# ISP_Arduino_Board.net
KiCad netlist of a schematic drawn in EAGLE
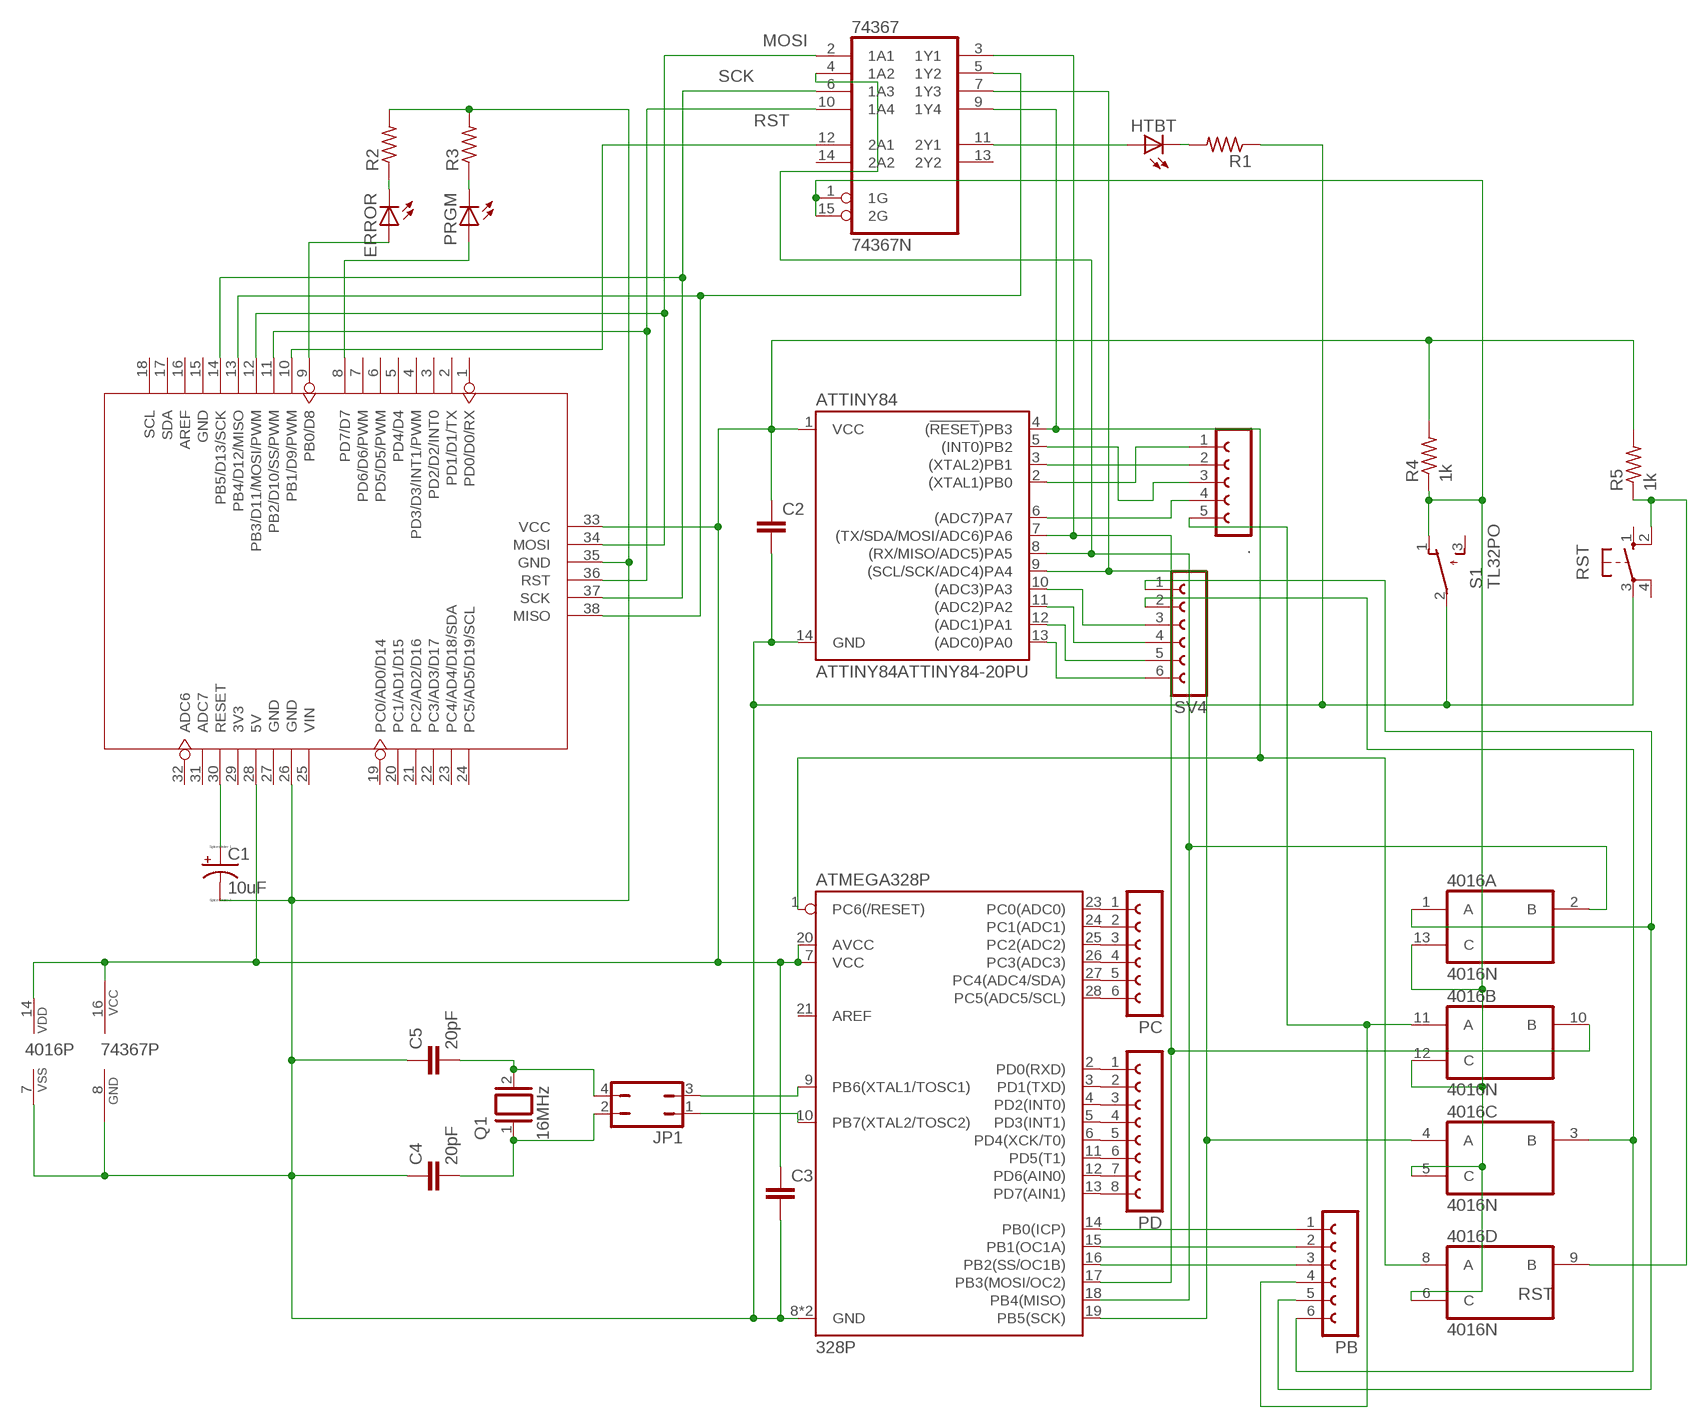
[diagram p0: schematic, sheet 1]

(export (version "E")
  (design (tool "Eeschema 10.0.6"))
  (components
    (comp (ref ".")
      (value "FE05-1")
      (footprint "eagle-import:FE05-1")
      (libsource (lib "eagle-import") (part "FE05-1"))
    )
    (comp (ref "4016")
      (value "4016N")
      (footprint "eagle-import:DIL14")
      (libsource (lib "eagle-import") (part "4016N"))
    )
    (comp (ref "74367")
      (value "74367N")
      (footprint "eagle-import:DIL16")
      (libsource (lib "eagle-import") (part "74367N"))
    )
    (comp (ref "ATMEGA328P")
      (value "328P")
      (footprint "eagle-import:DIP28")
      (libsource (lib "eagle-import") (part "ATMEGA328P_PDIP"))
    )
    (comp (ref "ATTINY84")
      (value "ATTINY84ATTINY84-20PU")
      (footprint "eagle-import:DIP14")
      (libsource (lib "eagle-import") (part "ATTINY84ATTINY84-20PU"))
    )
    (comp (ref "C1")
      (value "10uF")
      (footprint "eagle-import:E2,5-6")
      (libsource (lib "eagle-import") (part "CPOL-USE2.5-6"))
    )
    (comp (ref "C2")
      (value "C2,5-3")
      (footprint "eagle-import:C2.5-3")
      (libsource (lib "eagle-import") (part "C2,5-3"))
    )
    (comp (ref "C3")
      (value "C2,5-3")
      (footprint "eagle-import:C2.5-3")
      (libsource (lib "eagle-import") (part "C2,5-3"))
    )
    (comp (ref "C4")
      (value "20pF")
      (footprint "eagle-import:C2.5-3")
      (libsource (lib "eagle-import") (part "C2,5-3"))
    )
    (comp (ref "C5")
      (value "20pF")
      (footprint "eagle-import:C2.5-3")
      (libsource (lib "eagle-import") (part "C2,5-3"))
    )
    (comp (ref "ERROR")
      (value "LED3MM")
      (footprint "eagle-import:LED3MM")
      (libsource (lib "eagle-import") (part "LED3MM"))
    )
    (comp (ref "HTBT")
      (value "LED3MM")
      (footprint "eagle-import:LED3MM")
      (libsource (lib "eagle-import") (part "LED3MM"))
    )
    (comp (ref "JP1")
      (value "JP2Q")
      (footprint "eagle-import:JP2Q")
      (libsource (lib "eagle-import") (part "JP2Q"))
    )
    (comp (ref "PB")
      (value "FE06-1")
      (footprint "eagle-import:FE06")
      (libsource (lib "eagle-import") (part "FE06-1"))
    )
    (comp (ref "PC")
      (value "FE06-1")
      (footprint "eagle-import:FE06")
      (libsource (lib "eagle-import") (part "FE06-1"))
    )
    (comp (ref "PD")
      (value "FE08-1")
      (footprint "eagle-import:FE08")
      (libsource (lib "eagle-import") (part "FE08-1"))
    )
    (comp (ref "PRGM")
      (value "LED3MM")
      (footprint "eagle-import:LED3MM")
      (libsource (lib "eagle-import") (part "LED3MM"))
    )
    (comp (ref "Q1")
      (value "16MHz")
      (footprint "eagle-import:QS")
      (libsource (lib "eagle-import") (part "XTAL/S"))
    )
    (comp (ref "R1")
      (value "R-US_0207/10")
      (footprint "eagle-import:0207_10")
      (libsource (lib "eagle-import") (part "R-US_0207/10"))
    )
    (comp (ref "R2")
      (value "R-US_0207/10")
      (footprint "eagle-import:0207_10")
      (libsource (lib "eagle-import") (part "R-US_0207/10"))
    )
    (comp (ref "R3")
      (value "R-US_0207/10")
      (footprint "eagle-import:0207_10")
      (libsource (lib "eagle-import") (part "R-US_0207/10"))
    )
    (comp (ref "R4")
      (value "1k")
      (footprint "eagle-import:0207_10")
      (libsource (lib "eagle-import") (part "R-US_0207/10"))
    )
    (comp (ref "R5")
      (value "1k")
      (footprint "eagle-import:0207_10")
      (libsource (lib "eagle-import") (part "R-US_0207/10"))
    )
    (comp (ref "RST")
      (value "10-XX")
      (footprint "eagle-import:B3F-10XX")
      (fields (field (name "MPN") "B3F-1000"))
      (libsource (lib "eagle-import") (part "10-XX"))
    )
    (comp (ref "S1")
      (value "TL32PO")
      (footprint "eagle-import:TL3XPO")
      (libsource (lib "eagle-import") (part "TL32PO"))
    )
    (comp (ref "SV4")
      (value "FE06-1")
      (footprint "eagle-import:FE06")
      (libsource (lib "eagle-import") (part "FE06-1"))
    )
    (comp (ref "U2")
      (value "DIP Long Blue Female Header")
      (footprint "eagle-import:ARDUINO-38P")
      (libsource (lib "eagle-import") (part "ARDUINO-38P"))
    )
  )
  (nets
    (net (code "1") (name "Net-(4016A-A)") (class "Default")
      (node (ref "4016") (pin "1") (pinfunction "A_1") (pintype "tri_state"))
      (node (ref "PB") (pin "5") (pinfunction "5_5") (pintype "passive"))
      (node (ref "SV4") (pin "1") (pinfunction "1_1") (pintype "passive"))
    )
    (net (code "2") (name "Net-(4016A-B)") (class "Default")
      (node (ref "4016") (pin "2") (pinfunction "B_2") (pintype "tri_state"))
      (node (ref "74367") (pin "4") (pinfunction "1A2_4") (pintype "input"))
      (node (ref "ATMEGA328P") (pin "18") (pinfunction "PB4(MISO)_18") (pintype "bidirectional"))
      (node (ref "ATTINY84") (pin "8") (pinfunction "(RX/MISO/ADC5)PA5_8") (pintype "bidirectional"))
    )
    (net (code "3") (name "Net-(4016A-C)") (class "Default")
      (node (ref "4016") (pin "12") (pinfunction "C_12") (pintype "input"))
      (node (ref "4016") (pin "13") (pinfunction "C_13") (pintype "input"))
      (node (ref "4016") (pin "5") (pinfunction "C_5") (pintype "input"))
      (node (ref "4016") (pin "6") (pinfunction "C_6") (pintype "input"))
      (node (ref "74367") (pin "1") (pinfunction "1G_1") (pintype "input"))
      (node (ref "74367") (pin "15") (pinfunction "2G_15") (pintype "input"))
      (node (ref "R4") (pin "1") (pinfunction "1_1") (pintype "passive"))
      (node (ref "S1") (pin "1") (pinfunction "O_1") (pintype "passive"))
    )
    (net (code "4") (name "Net-(4016B-A)") (class "Default")
      (node (ref ".") (pin "5") (pinfunction "5_5") (pintype "passive"))
      (node (ref "4016") (pin "11") (pinfunction "A_11") (pintype "tri_state"))
      (node (ref "PB") (pin "4") (pinfunction "4_4") (pintype "passive"))
    )
    (net (code "5") (name "Net-(4016B-B)") (class "Default")
      (node (ref "4016") (pin "10") (pinfunction "B_10") (pintype "tri_state"))
      (node (ref "74367") (pin "3") (pinfunction "1Y1_3") (pintype "tri_state"))
      (node (ref "ATMEGA328P") (pin "17") (pinfunction "PB3(MOSI/OC2)_17") (pintype "bidirectional"))
      (node (ref "ATTINY84") (pin "7") (pinfunction "(TX/SDA/MOSI/ADC6)PA6_7") (pintype "bidirectional"))
    )
    (net (code "6") (name "Net-(4016C-A)") (class "Default")
      (node (ref "4016") (pin "4") (pinfunction "A_4") (pintype "tri_state"))
      (node (ref "74367") (pin "7") (pinfunction "1Y3_7") (pintype "tri_state"))
      (node (ref "ATMEGA328P") (pin "19") (pinfunction "PB5(SCK)_19") (pintype "bidirectional"))
      (node (ref "ATTINY84") (pin "9") (pinfunction "(SCL/SCK/ADC4)PA4_9") (pintype "bidirectional"))
    )
    (net (code "7") (name "Net-(4016C-B)") (class "Default")
      (node (ref "4016") (pin "3") (pinfunction "B_3") (pintype "tri_state"))
      (node (ref "PB") (pin "6") (pinfunction "6_6") (pintype "passive"))
      (node (ref "SV4") (pin "2") (pinfunction "2_2") (pintype "passive"))
    )
    (net (code "8") (name "Net-(4016D-B)") (class "Default")
      (node (ref "4016") (pin "9") (pinfunction "B_9") (pintype "tri_state"))
      (node (ref "R5") (pin "1") (pinfunction "1_1") (pintype "passive"))
      (node (ref "RST") (pin "2") (pinfunction "S1_2") (pintype "passive"))
    )
    (net (code "9") (name "Net-(4016E-VDD)") (class "Default")
      (node (ref "4016") (pin "14") (pinfunction "VDD_14") (pintype "power_in"))
      (node (ref "74367") (pin "16") (pinfunction "VCC_16") (pintype "power_in"))
      (node (ref "ATMEGA328P") (pin "20") (pinfunction "AVCC_20") (pintype "bidirectional"))
      (node (ref "ATMEGA328P") (pin "7") (pinfunction "VCC_7") (pintype "bidirectional"))
      (node (ref "ATTINY84") (pin "1") (pinfunction "VCC_1") (pintype "bidirectional"))
      (node (ref "C2") (pin "1") (pinfunction "1_1") (pintype "passive"))
      (node (ref "C3") (pin "1") (pinfunction "1_1") (pintype "passive"))
      (node (ref "R4") (pin "2") (pinfunction "2_2") (pintype "passive"))
      (node (ref "R5") (pin "2") (pinfunction "2_2") (pintype "passive"))
      (node (ref "U2") (pin "28") (pinfunction "5V_28") (pintype "bidirectional"))
      (node (ref "U2") (pin "33") (pinfunction "VCC_33") (pintype "bidirectional"))
    )
    (net (code "10") (name "Net-(4016E-VSS)") (class "Default")
      (node (ref "4016") (pin "7") (pinfunction "VSS_7") (pintype "power_in"))
      (node (ref "74367") (pin "8") (pinfunction "GND_8") (pintype "power_in"))
      (node (ref "ATMEGA328P") (pin "22") (pinfunction "GND_22") (pintype "bidirectional"))
      (node (ref "ATMEGA328P") (pin "8") (pinfunction "GND_8") (pintype "bidirectional"))
      (node (ref "ATTINY84") (pin "14") (pinfunction "GND_14") (pintype "bidirectional"))
      (node (ref "C1") (pin "-") (pinfunction "-_-") (pintype "passive"))
      (node (ref "C2") (pin "2") (pinfunction "2_2") (pintype "passive"))
      (node (ref "C3") (pin "2") (pinfunction "2_2") (pintype "passive"))
      (node (ref "C4") (pin "1") (pinfunction "1_1") (pintype "passive"))
      (node (ref "C5") (pin "1") (pinfunction "1_1") (pintype "passive"))
      (node (ref "R1") (pin "1") (pinfunction "1_1") (pintype "passive"))
      (node (ref "R2") (pin "2") (pinfunction "2_2") (pintype "passive"))
      (node (ref "R3") (pin "2") (pinfunction "2_2") (pintype "passive"))
      (node (ref "RST") (pin "3") (pinfunction "P_3") (pintype "passive"))
      (node (ref "S1") (pin "2") (pinfunction "P_2") (pintype "passive"))
      (node (ref "U2") (pin "26") (pinfunction "GND_26") (pintype "bidirectional"))
      (node (ref "U2") (pin "35") (pinfunction "GND_35") (pintype "bidirectional"))
    )
    (net (code "11") (name "Net-(74367A-1A1)") (class "Default")
      (node (ref "74367") (pin "2") (pinfunction "1A1_2") (pintype "input"))
      (node (ref "U2") (pin "12") (pinfunction "PB3/D11/MOSI/PWM_12") (pintype "bidirectional"))
      (node (ref "U2") (pin "34") (pinfunction "MOSI_34") (pintype "bidirectional"))
    )
    (net (code "12") (name "Net-(74367A-1A3)") (class "Default")
      (node (ref "74367") (pin "6") (pinfunction "1A3_6") (pintype "input"))
      (node (ref "U2") (pin "14") (pinfunction "PB5/D13/SCK_14") (pintype "bidirectional"))
      (node (ref "U2") (pin "37") (pinfunction "SCK_37") (pintype "bidirectional"))
    )
    (net (code "13") (name "Net-(74367A-1A4)") (class "Default")
      (node (ref "74367") (pin "10") (pinfunction "1A4_10") (pintype "input"))
      (node (ref "U2") (pin "11") (pinfunction "PB2/D10/SS/PWM_11") (pintype "bidirectional"))
      (node (ref "U2") (pin "36") (pinfunction "RST_36") (pintype "bidirectional"))
    )
    (net (code "14") (name "Net-(74367A-1Y2)") (class "Default")
      (node (ref "74367") (pin "5") (pinfunction "1Y2_5") (pintype "tri_state"))
      (node (ref "U2") (pin "13") (pinfunction "PB4/D12/MISO_13") (pintype "bidirectional"))
      (node (ref "U2") (pin "38") (pinfunction "MISO_38") (pintype "bidirectional"))
    )
    (net (code "15") (name "Net-(74367A-1Y4)") (class "Default")
      (node (ref "74367") (pin "9") (pinfunction "1Y4_9") (pintype "tri_state"))
      (node (ref "ATMEGA328P") (pin "1") (pinfunction "PC6(/RESET)_1") (pintype "bidirectional"))
      (node (ref "ATTINY84") (pin "4") (pinfunction "(~{RESET})PB3_4") (pintype "bidirectional"))
    )
    (net (code "16") (name "Net-(74367A-2A1)") (class "Default")
      (node (ref "74367") (pin "12") (pinfunction "2A1_12") (pintype "input"))
      (node (ref "U2") (pin "10") (pinfunction "PB1/D9/PWM_10") (pintype "bidirectional"))
    )
    (net (code "17") (name "Net-(74367A-2Y1)") (class "Default")
      (node (ref "74367") (pin "11") (pinfunction "2Y1_11") (pintype "tri_state"))
      (node (ref "HTBT") (pin "A") (pinfunction "A_A") (pintype "passive"))
    )
    (net (code "18") (name "Net-(ATMEGA328P-PB0(ICP))") (class "Default")
      (node (ref "ATMEGA328P") (pin "14") (pinfunction "PB0(ICP)_14") (pintype "bidirectional"))
      (node (ref "PB") (pin "1") (pinfunction "1_1") (pintype "passive"))
    )
    (net (code "19") (name "Net-(ATMEGA328P-PB1(OC1A))") (class "Default")
      (node (ref "ATMEGA328P") (pin "15") (pinfunction "PB1(OC1A)_15") (pintype "bidirectional"))
      (node (ref "PB") (pin "2") (pinfunction "2_2") (pintype "passive"))
    )
    (net (code "20") (name "Net-(ATMEGA328P-PB2(SS{slash}OC1B))") (class "Default")
      (node (ref "ATMEGA328P") (pin "16") (pinfunction "PB2(SS/OC1B)_16") (pintype "bidirectional"))
      (node (ref "PB") (pin "3") (pinfunction "3_3") (pintype "passive"))
    )
    (net (code "21") (name "Net-(ATMEGA328P-PB6(XTAL1{slash}TOSC1))") (class "Default")
      (node (ref "ATMEGA328P") (pin "9") (pinfunction "PB6(XTAL1/TOSC1)_9") (pintype "bidirectional"))
      (node (ref "JP1") (pin "3") (pinfunction "3_3") (pintype "passive"))
    )
    (net (code "22") (name "Net-(ATMEGA328P-PB7(XTAL2{slash}TOSC2))") (class "Default")
      (node (ref "ATMEGA328P") (pin "10") (pinfunction "PB7(XTAL2/TOSC2)_10") (pintype "bidirectional"))
      (node (ref "JP1") (pin "1") (pinfunction "1_1") (pintype "passive"))
    )
    (net (code "23") (name "Net-(ATMEGA328P-PC0(ADC0))") (class "Default")
      (node (ref "ATMEGA328P") (pin "23") (pinfunction "PC0(ADC0)_23") (pintype "bidirectional"))
      (node (ref "PC") (pin "1") (pinfunction "1_1") (pintype "passive"))
    )
    (net (code "24") (name "Net-(ATMEGA328P-PC1(ADC1))") (class "Default")
      (node (ref "ATMEGA328P") (pin "24") (pinfunction "PC1(ADC1)_24") (pintype "bidirectional"))
      (node (ref "PC") (pin "2") (pinfunction "2_2") (pintype "passive"))
    )
    (net (code "25") (name "Net-(ATMEGA328P-PC2(ADC2))") (class "Default")
      (node (ref "ATMEGA328P") (pin "25") (pinfunction "PC2(ADC2)_25") (pintype "bidirectional"))
      (node (ref "PC") (pin "3") (pinfunction "3_3") (pintype "passive"))
    )
    (net (code "26") (name "Net-(ATMEGA328P-PC3(ADC3))") (class "Default")
      (node (ref "ATMEGA328P") (pin "26") (pinfunction "PC3(ADC3)_26") (pintype "bidirectional"))
      (node (ref "PC") (pin "4") (pinfunction "4_4") (pintype "passive"))
    )
    (net (code "27") (name "Net-(ATMEGA328P-PC4(ADC4{slash}SDA))") (class "Default")
      (node (ref "ATMEGA328P") (pin "27") (pinfunction "PC4(ADC4/SDA)_27") (pintype "bidirectional"))
      (node (ref "PC") (pin "5") (pinfunction "5_5") (pintype "passive"))
    )
    (net (code "28") (name "Net-(ATMEGA328P-PC5(ADC5{slash}SCL))") (class "Default")
      (node (ref "ATMEGA328P") (pin "28") (pinfunction "PC5(ADC5/SCL)_28") (pintype "bidirectional"))
      (node (ref "PC") (pin "6") (pinfunction "6_6") (pintype "passive"))
    )
    (net (code "29") (name "Net-(ATMEGA328P-PD0(RXD))") (class "Default")
      (node (ref "ATMEGA328P") (pin "2") (pinfunction "PD0(RXD)_2") (pintype "bidirectional"))
      (node (ref "PD") (pin "1") (pinfunction "1_1") (pintype "passive"))
    )
    (net (code "30") (name "Net-(ATMEGA328P-PD1(TXD))") (class "Default")
      (node (ref "ATMEGA328P") (pin "3") (pinfunction "PD1(TXD)_3") (pintype "bidirectional"))
      (node (ref "PD") (pin "2") (pinfunction "2_2") (pintype "passive"))
    )
    (net (code "31") (name "Net-(ATMEGA328P-PD2(INT0))") (class "Default")
      (node (ref "ATMEGA328P") (pin "4") (pinfunction "PD2(INT0)_4") (pintype "bidirectional"))
      (node (ref "PD") (pin "3") (pinfunction "3_3") (pintype "passive"))
    )
    (net (code "32") (name "Net-(ATMEGA328P-PD3(INT1))") (class "Default")
      (node (ref "ATMEGA328P") (pin "5") (pinfunction "PD3(INT1)_5") (pintype "bidirectional"))
      (node (ref "PD") (pin "4") (pinfunction "4_4") (pintype "passive"))
    )
    (net (code "33") (name "Net-(ATMEGA328P-PD4(XCK{slash}T0))") (class "Default")
      (node (ref "ATMEGA328P") (pin "6") (pinfunction "PD4(XCK/T0)_6") (pintype "bidirectional"))
      (node (ref "PD") (pin "5") (pinfunction "5_5") (pintype "passive"))
    )
    (net (code "34") (name "Net-(ATMEGA328P-PD5(T1))") (class "Default")
      (node (ref "ATMEGA328P") (pin "11") (pinfunction "PD5(T1)_11") (pintype "bidirectional"))
      (node (ref "PD") (pin "6") (pinfunction "6_6") (pintype "passive"))
    )
    (net (code "35") (name "Net-(ATMEGA328P-PD6(AIN0))") (class "Default")
      (node (ref "ATMEGA328P") (pin "12") (pinfunction "PD6(AIN0)_12") (pintype "bidirectional"))
      (node (ref "PD") (pin "7") (pinfunction "7_7") (pintype "passive"))
    )
    (net (code "36") (name "Net-(ATMEGA328P-PD7(AIN1))") (class "Default")
      (node (ref "ATMEGA328P") (pin "13") (pinfunction "PD7(AIN1)_13") (pintype "bidirectional"))
      (node (ref "PD") (pin "8") (pinfunction "8_8") (pintype "passive"))
    )
    (net (code "37") (name "Net-(ATTINY84-(ADC0)PA0)") (class "Default")
      (node (ref "ATTINY84") (pin "13") (pinfunction "(ADC0)PA0_13") (pintype "bidirectional"))
      (node (ref "SV4") (pin "6") (pinfunction "6_6") (pintype "passive"))
    )
    (net (code "38") (name "Net-(ATTINY84-(ADC1)PA1)") (class "Default")
      (node (ref "ATTINY84") (pin "12") (pinfunction "(ADC1)PA1_12") (pintype "bidirectional"))
      (node (ref "SV4") (pin "5") (pinfunction "5_5") (pintype "passive"))
    )
    (net (code "39") (name "Net-(ATTINY84-(ADC2)PA2)") (class "Default")
      (node (ref "ATTINY84") (pin "11") (pinfunction "(ADC2)PA2_11") (pintype "bidirectional"))
      (node (ref "SV4") (pin "4") (pinfunction "4_4") (pintype "passive"))
    )
    (net (code "40") (name "Net-(ATTINY84-(ADC3)PA3)") (class "Default")
      (node (ref "ATTINY84") (pin "10") (pinfunction "(ADC3)PA3_10") (pintype "bidirectional"))
      (node (ref "SV4") (pin "3") (pinfunction "3_3") (pintype "passive"))
    )
    (net (code "41") (name "Net-(ATTINY84-(ADC7)PA7)") (class "Default")
      (node (ref ".") (pin "4") (pinfunction "4_4") (pintype "passive"))
      (node (ref "ATTINY84") (pin "6") (pinfunction "(ADC7)PA7_6") (pintype "bidirectional"))
    )
    (net (code "42") (name "Net-(ATTINY84-(INT0)PB2)") (class "Default")
      (node (ref ".") (pin "3") (pinfunction "3_3") (pintype "passive"))
      (node (ref "ATTINY84") (pin "5") (pinfunction "(INT0)PB2_5") (pintype "bidirectional"))
    )
    (net (code "43") (name "Net-(ATTINY84-(XTAL1)PB0)") (class "Default")
      (node (ref ".") (pin "1") (pinfunction "1_1") (pintype "passive"))
      (node (ref "ATTINY84") (pin "2") (pinfunction "(XTAL1)PB0_2") (pintype "bidirectional"))
    )
    (net (code "44") (name "Net-(ATTINY84-(XTAL2)PB1)") (class "Default")
      (node (ref ".") (pin "2") (pinfunction "2_2") (pintype "passive"))
      (node (ref "ATTINY84") (pin "3") (pinfunction "(XTAL2)PB1_3") (pintype "bidirectional"))
    )
    (net (code "45") (name "Net-(C4-Pad2)") (class "Default")
      (node (ref "C4") (pin "2") (pinfunction "2_2") (pintype "passive"))
      (node (ref "JP1") (pin "2") (pinfunction "2_2") (pintype "passive"))
      (node (ref "Q1") (pin "1") (pinfunction "1_1") (pintype "passive"))
    )
    (net (code "46") (name "Net-(C5-Pad2)") (class "Default")
      (node (ref "C5") (pin "2") (pinfunction "2_2") (pintype "passive"))
      (node (ref "JP1") (pin "4") (pinfunction "4_4") (pintype "passive"))
      (node (ref "Q1") (pin "2") (pinfunction "2_2") (pintype "passive"))
    )
    (net (code "47") (name "Net-(ERROR-C)") (class "Default")
      (node (ref "ERROR") (pin "K") (pinfunction "C_K") (pintype "passive"))
      (node (ref "R2") (pin "1") (pinfunction "1_1") (pintype "passive"))
    )
    (net (code "48") (name "Net-(HTBT-C)") (class "Default")
      (node (ref "HTBT") (pin "K") (pinfunction "C_K") (pintype "passive"))
      (node (ref "R1") (pin "2") (pinfunction "2_2") (pintype "passive"))
    )
    (net (code "49") (name "Net-(PRGM-C)") (class "Default")
      (node (ref "PRGM") (pin "K") (pinfunction "C_K") (pintype "passive"))
      (node (ref "R3") (pin "1") (pinfunction "1_1") (pintype "passive"))
    )
    (net (code "50") (name "Net-(U2-PB0{slash}D8)") (class "Default")
      (node (ref "ERROR") (pin "A") (pinfunction "A_A") (pintype "passive"))
      (node (ref "U2") (pin "9") (pinfunction "PB0/D8_9") (pintype "bidirectional"))
    )
    (net (code "51") (name "Net-(U2-PD7{slash}D7)") (class "Default")
      (node (ref "PRGM") (pin "A") (pinfunction "A_A") (pintype "passive"))
      (node (ref "U2") (pin "8") (pinfunction "PD7/D7_8") (pintype "bidirectional"))
    )
    (net (code "52") (name "Net-(U2-RESET)") (class "Default")
      (node (ref "C1") (pin "+") (pinfunction "+_+") (pintype "passive"))
      (node (ref "U2") (pin "30") (pinfunction "RESET_30") (pintype "bidirectional"))
    )
    (net (code "53") (name "unconnected-(4016D-A-Pad8)") (class "Default")
      (node (ref "4016") (pin "8") (pinfunction "A_8") (pintype "tri_state"))
    )
    (net (code "54") (name "unconnected-(74367A-2A2-Pad14)") (class "Default")
      (node (ref "74367") (pin "14") (pinfunction "2A2_14") (pintype "input"))
    )
    (net (code "55") (name "unconnected-(74367A-2Y2-Pad13)") (class "Default")
      (node (ref "74367") (pin "13") (pinfunction "2Y2_13") (pintype "tri_state"))
    )
    (net (code "56") (name "unconnected-(ATMEGA328P-AREF-Pad21)") (class "Default")
      (node (ref "ATMEGA328P") (pin "21") (pinfunction "AREF_21") (pintype "bidirectional"))
    )
    (net (code "57") (name "unconnected-(RST-P1-Pad4)") (class "Default")
      (node (ref "RST") (pin "4") (pinfunction "P1_4") (pintype "passive"))
    )
    (net (code "58") (name "unconnected-(RST-S-Pad1)") (class "Default")
      (node (ref "RST") (pin "1") (pinfunction "S_1") (pintype "passive"))
    )
    (net (code "59") (name "unconnected-(S1-S-Pad3)") (class "Default")
      (node (ref "S1") (pin "3") (pinfunction "S_3") (pintype "passive"))
    )
    (net (code "60") (name "unconnected-(U2-3V3-Pad29)") (class "Default")
      (node (ref "U2") (pin "29") (pinfunction "3V3_29") (pintype "bidirectional"))
    )
    (net (code "61") (name "unconnected-(U2-ADC6-Pad32)") (class "Default")
      (node (ref "U2") (pin "32") (pinfunction "ADC6_32") (pintype "bidirectional"))
    )
    (net (code "62") (name "unconnected-(U2-ADC7-Pad31)") (class "Default")
      (node (ref "U2") (pin "31") (pinfunction "ADC7_31") (pintype "bidirectional"))
    )
    (net (code "63") (name "unconnected-(U2-AREF-Pad16)") (class "Default")
      (node (ref "U2") (pin "16") (pinfunction "AREF_16") (pintype "bidirectional"))
    )
    (net (code "64") (name "unconnected-(U2-GND-Pad15)") (class "Default")
      (node (ref "U2") (pin "15") (pinfunction "GND_15") (pintype "bidirectional"))
    )
    (net (code "65") (name "unconnected-(U2-GND-Pad27)") (class "Default")
      (node (ref "U2") (pin "27") (pinfunction "GND_27") (pintype "bidirectional"))
    )
    (net (code "66") (name "unconnected-(U2-PC0{slash}AD0{slash}D14-Pad19)") (class "Default")
      (node (ref "U2") (pin "19") (pinfunction "PC0/AD0/D14_19") (pintype "bidirectional"))
    )
    (net (code "67") (name "unconnected-(U2-PC1{slash}AD1{slash}D15-Pad20)") (class "Default")
      (node (ref "U2") (pin "20") (pinfunction "PC1/AD1/D15_20") (pintype "bidirectional"))
    )
    (net (code "68") (name "unconnected-(U2-PC2{slash}AD2{slash}D16-Pad21)") (class "Default")
      (node (ref "U2") (pin "21") (pinfunction "PC2/AD2/D16_21") (pintype "bidirectional"))
    )
    (net (code "69") (name "unconnected-(U2-PC3{slash}AD3{slash}D17-Pad22)") (class "Default")
      (node (ref "U2") (pin "22") (pinfunction "PC3/AD3/D17_22") (pintype "bidirectional"))
    )
    (net (code "70") (name "unconnected-(U2-PC4{slash}AD4{slash}D18{slash}SDA-Pad23)") (class "Default")
      (node (ref "U2") (pin "23") (pinfunction "PC4/AD4/D18/SDA_23") (pintype "bidirectional"))
    )
    (net (code "71") (name "unconnected-(U2-PC5{slash}AD5{slash}D19{slash}SCL-Pad24)") (class "Default")
      (node (ref "U2") (pin "24") (pinfunction "PC5/AD5/D19/SCL_24") (pintype "bidirectional"))
    )
    (net (code "72") (name "unconnected-(U2-PD0{slash}D0{slash}RX-Pad1)") (class "Default")
      (node (ref "U2") (pin "1") (pinfunction "PD0/D0/RX_1") (pintype "bidirectional"))
    )
    (net (code "73") (name "unconnected-(U2-PD1{slash}D1{slash}TX-Pad2)") (class "Default")
      (node (ref "U2") (pin "2") (pinfunction "PD1/D1/TX_2") (pintype "bidirectional"))
    )
    (net (code "74") (name "unconnected-(U2-PD2{slash}D2{slash}INT0-Pad3)") (class "Default")
      (node (ref "U2") (pin "3") (pinfunction "PD2/D2/INT0_3") (pintype "bidirectional"))
    )
    (net (code "75") (name "unconnected-(U2-PD3{slash}D3{slash}INT1{slash}PWM-Pad4)") (class "Default")
      (node (ref "U2") (pin "4") (pinfunction "PD3/D3/INT1/PWM_4") (pintype "bidirectional"))
    )
    (net (code "76") (name "unconnected-(U2-PD4{slash}D4-Pad5)") (class "Default")
      (node (ref "U2") (pin "5") (pinfunction "PD4/D4_5") (pintype "bidirectional"))
    )
    (net (code "77") (name "unconnected-(U2-PD5{slash}D5{slash}PWM-Pad6)") (class "Default")
      (node (ref "U2") (pin "6") (pinfunction "PD5/D5/PWM_6") (pintype "bidirectional"))
    )
    (net (code "78") (name "unconnected-(U2-PD6{slash}D6{slash}PWM-Pad7)") (class "Default")
      (node (ref "U2") (pin "7") (pinfunction "PD6/D6/PWM_7") (pintype "bidirectional"))
    )
    (net (code "79") (name "unconnected-(U2-SCL-Pad18)") (class "Default")
      (node (ref "U2") (pin "18") (pinfunction "SCL_18") (pintype "bidirectional"))
    )
    (net (code "80") (name "unconnected-(U2-SDA-Pad17)") (class "Default")
      (node (ref "U2") (pin "17") (pinfunction "SDA_17") (pintype "bidirectional"))
    )
    (net (code "81") (name "unconnected-(U2-VIN-Pad25)") (class "Default")
      (node (ref "U2") (pin "25") (pinfunction "VIN_25") (pintype "bidirectional"))
    )
  )
)
